# Motor_Driver_HIP4082_Board_V1_3.net
KiCad netlist of a schematic drawn in Altium Designer
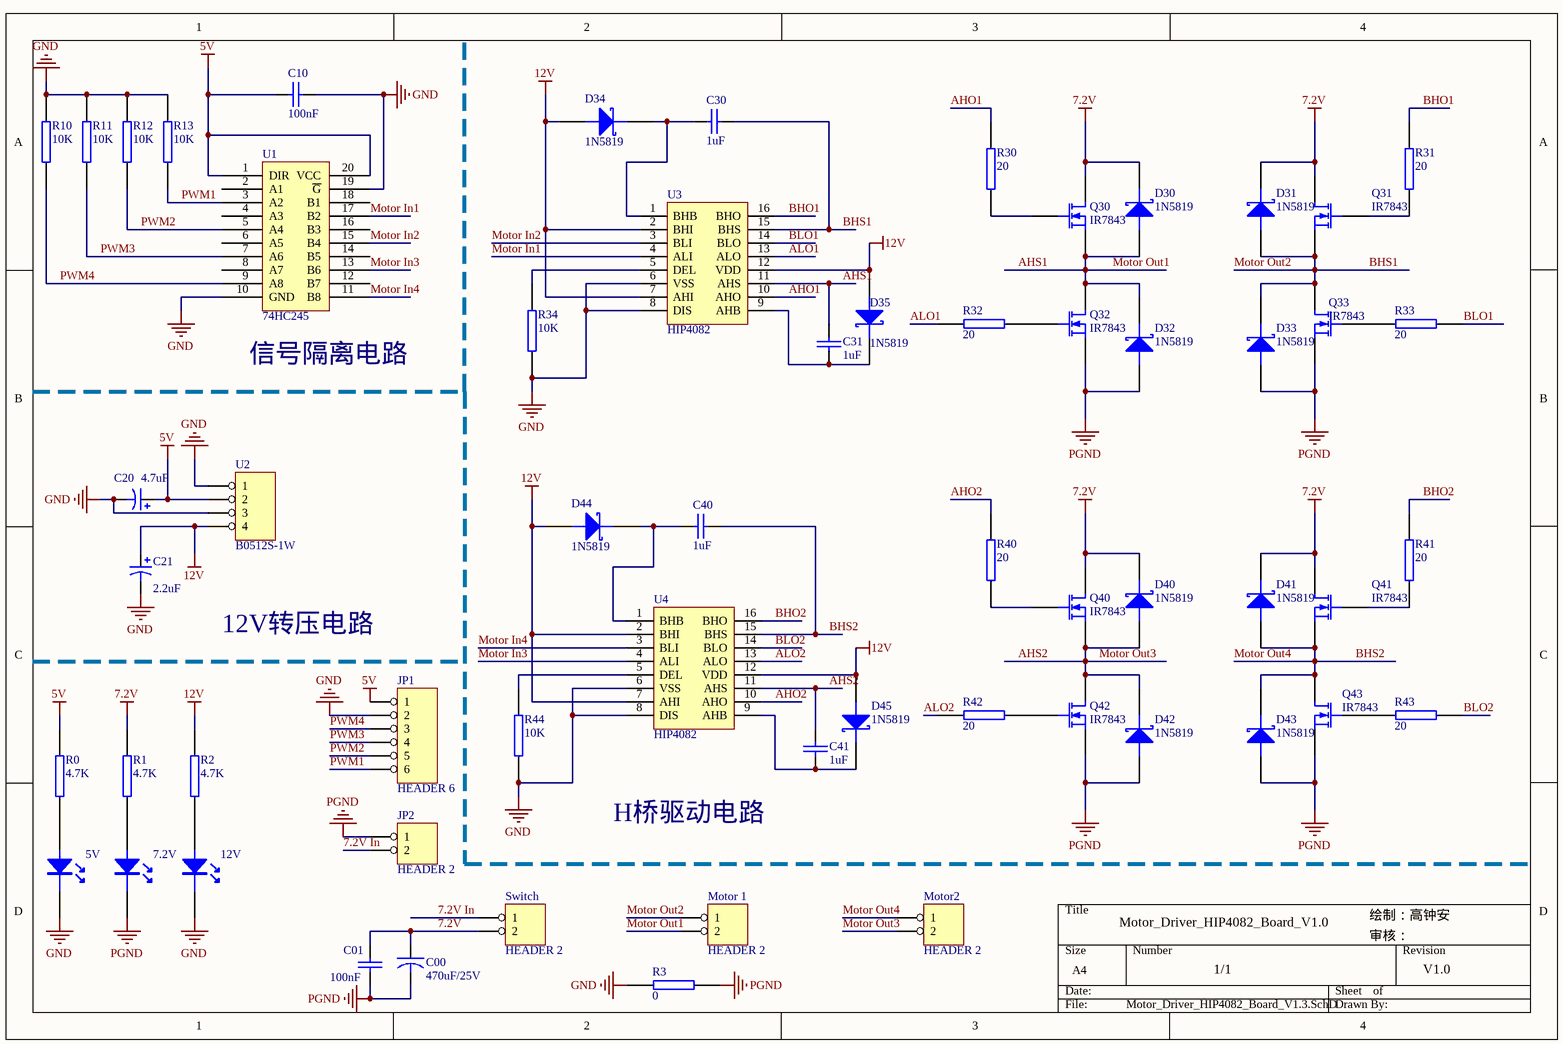
[diagram p0: Motor_Driver_HIP4082_Board_V1.3.SchDoc]

(export (version "E")
  (design (tool "Eeschema 10.0.6"))
  (components
    (comp (ref "5V") (value "~") (footprint "0805_LED_S1") (libsource (lib "Protel99Lib_SCH") (part "LED")))
    (comp (ref "7.2V") (value "~") (footprint "0805_LED_S1") (libsource (lib "Protel99Lib_SCH") (part "LED")))
    (comp (ref "12V") (value "~") (footprint "0805_LED_S1") (libsource (lib "Protel99Lib_SCH") (part "LED")))
    (comp (ref "C00")
      (value "470uF/25V")
      (footprint "RB.2/.4")
      (description "Capacitor")
      (libsource (lib "Protel99Lib_SCH") (part "CAPACITOR"))
    )
    (comp (ref "C01")
      (value "100nF")
      (footprint "0805C")
      (description "Capacitor")
      (libsource (lib "Protel99Lib_SCH") (part "CAP"))
    )
    (comp (ref "C10")
      (value "100nF")
      (footprint "0603_C")
      (description "Capacitor")
      (libsource (lib "Protel99Lib_SCH") (part "CAP"))
    )
    (comp (ref "C20")
      (value "4.7uF")
      (footprint "3528")
      (description "Polarized Capacitor (Surface Mount)")
      (fields (field (name "PUBLISHER") "Altium Limited"))
      (libsource (lib "Miscellaneous Devices") (part "Cap Pol3"))
    )
    (comp (ref "C21")
      (value "2.2uF")
      (footprint "3528")
      (description "Polarized Capacitor (Surface Mount)")
      (fields (field (name "PUBLISHER") "Altium Limited"))
      (libsource (lib "Miscellaneous Devices") (part "Cap Pol3"))
    )
    (comp (ref "C30")
      (value "1uF")
      (footprint "0603C")
      (description "Capacitor")
      (libsource (lib "Protel99Lib_SCH") (part "CAP"))
    )
    (comp (ref "C31")
      (value "1uF")
      (footprint "0603C")
      (description "Capacitor")
      (libsource (lib "Protel99Lib_SCH") (part "CAP"))
    )
    (comp (ref "C40")
      (value "1uF")
      (footprint "0603_C")
      (description "Capacitor")
      (libsource (lib "Protel99Lib_SCH") (part "CAP"))
    )
    (comp (ref "C41")
      (value "1uF")
      (footprint "0603_C")
      (description "Capacitor")
      (libsource (lib "Protel99Lib_SCH") (part "CAP"))
    )
    (comp (ref "D30")
      (value "1N5819")
      (footprint "SOD-323")
      (description "Schottky Diode")
      (libsource (lib "Protel99Lib_SCH") (part "DIODE SCHOTTKY"))
    )
    (comp (ref "D31")
      (value "1N5819")
      (footprint "SOD-323")
      (description "Schottky Diode")
      (libsource (lib "Protel99Lib_SCH") (part "DIODE SCHOTTKY"))
    )
    (comp (ref "D32")
      (value "1N5819")
      (footprint "SOD-323")
      (description "Schottky Diode")
      (libsource (lib "Protel99Lib_SCH") (part "DIODE SCHOTTKY"))
    )
    (comp (ref "D33")
      (value "1N5819")
      (footprint "SOD-323")
      (description "Schottky Diode")
      (libsource (lib "Protel99Lib_SCH") (part "DIODE SCHOTTKY"))
    )
    (comp (ref "D34")
      (value "1N5819")
      (footprint "SOD-323")
      (description "Schottky Diode")
      (libsource (lib "Protel99Lib_SCH") (part "DIODE SCHOTTKY"))
    )
    (comp (ref "D35")
      (value "1N5819")
      (footprint "SOD-323")
      (description "Schottky Diode")
      (libsource (lib "Protel99Lib_SCH") (part "DIODE SCHOTTKY"))
    )
    (comp (ref "D40")
      (value "1N5819")
      (footprint "SOD-323")
      (description "Schottky Diode")
      (libsource (lib "Protel99Lib_SCH") (part "DIODE SCHOTTKY"))
    )
    (comp (ref "D41")
      (value "1N5819")
      (footprint "SOD-323")
      (description "Schottky Diode")
      (libsource (lib "Protel99Lib_SCH") (part "DIODE SCHOTTKY"))
    )
    (comp (ref "D42")
      (value "1N5819")
      (footprint "SOD-323")
      (description "Schottky Diode")
      (libsource (lib "Protel99Lib_SCH") (part "DIODE SCHOTTKY"))
    )
    (comp (ref "D43")
      (value "1N5819")
      (footprint "SOD-323")
      (description "Schottky Diode")
      (libsource (lib "Protel99Lib_SCH") (part "DIODE SCHOTTKY"))
    )
    (comp (ref "D44")
      (value "1N5819")
      (footprint "SOD-323")
      (description "Schottky Diode")
      (libsource (lib "Protel99Lib_SCH") (part "DIODE SCHOTTKY"))
    )
    (comp (ref "D45")
      (value "1N5819")
      (footprint "SOD-323")
      (description "Schottky Diode")
      (libsource (lib "Protel99Lib_SCH") (part "DIODE SCHOTTKY"))
    )
    (comp (ref "JP1")
      (value "HEADER 6")
      (footprint "SIP6N")
      (libsource (lib "Protel99Lib_SCH") (part "HEADER 6"))
    )
    (comp (ref "JP2")
      (value "HEADER 2")
      (footprint "KF301-2P")
      (libsource (lib "Protel99Lib_SCH") (part "HEADER 2"))
    )
    (comp (ref "Motor 1")
      (value "HEADER 2")
      (footprint "KF301-2P")
      (libsource (lib "Protel99Lib_SCH") (part "HEADER 2"))
    )
    (comp (ref "Motor2")
      (value "HEADER 2")
      (footprint "KF301-2P")
      (libsource (lib "Protel99Lib_SCH") (part "HEADER 2"))
    )
    (comp (ref "Q30")
      (value "IR7843")
      (footprint "LR7843")
      (description "N-Channel MOSFET")
      (fields (field (name "PUBLISHER") "Altium Limited"))
      (libsource (lib "Miscellaneous Devices") (part "MOSFET-N"))
    )
    (comp (ref "Q31")
      (value "IR7843")
      (footprint "LR7843")
      (description "N-Channel MOSFET")
      (fields (field (name "PUBLISHER") "Altium Limited"))
      (libsource (lib "Miscellaneous Devices") (part "MOSFET-N"))
    )
    (comp (ref "Q32")
      (value "IR7843")
      (footprint "LR7843")
      (description "N-Channel MOSFET")
      (fields (field (name "PUBLISHER") "Altium Limited"))
      (libsource (lib "Miscellaneous Devices") (part "MOSFET-N"))
    )
    (comp (ref "Q33")
      (value "IR7843")
      (footprint "LR7843")
      (description "N-Channel MOSFET")
      (fields (field (name "PUBLISHER") "Altium Limited"))
      (libsource (lib "Miscellaneous Devices") (part "MOSFET-N"))
    )
    (comp (ref "Q40")
      (value "IR7843")
      (footprint "LR7843")
      (description "N-Channel MOSFET")
      (fields (field (name "PUBLISHER") "Altium Limited"))
      (libsource (lib "Miscellaneous Devices") (part "MOSFET-N"))
    )
    (comp (ref "Q41")
      (value "IR7843")
      (footprint "LR7843")
      (description "N-Channel MOSFET")
      (fields (field (name "PUBLISHER") "Altium Limited"))
      (libsource (lib "Miscellaneous Devices") (part "MOSFET-N"))
    )
    (comp (ref "Q42")
      (value "IR7843")
      (footprint "LR7843")
      (description "N-Channel MOSFET")
      (fields (field (name "PUBLISHER") "Altium Limited"))
      (libsource (lib "Miscellaneous Devices") (part "MOSFET-N"))
    )
    (comp (ref "Q43")
      (value "IR7843")
      (footprint "LR7843")
      (description "N-Channel MOSFET")
      (fields (field (name "PUBLISHER") "Altium Limited"))
      (libsource (lib "Miscellaneous Devices") (part "MOSFET-N"))
    )
    (comp (ref "R0") (value "4.7K") (footprint "0603_R") (libsource (lib "") (part "RES2_1")))
    (comp (ref "R1") (value "4.7K") (footprint "0603_R") (libsource (lib "") (part "RES2_1")))
    (comp (ref "R2") (value "4.7K") (footprint "0603_R") (libsource (lib "") (part "RES2_1")))
    (comp (ref "R3") (value "0") (footprint "0805") (libsource (lib "") (part "RES2_1")))
    (comp (ref "R10") (value "10K") (footprint "0603_R") (libsource (lib "Protel99Lib_SCH") (part "RES2")))
    (comp (ref "R11") (value "10K") (footprint "0603_R") (libsource (lib "Protel99Lib_SCH") (part "RES2")))
    (comp (ref "R12") (value "10K") (footprint "0603_R") (libsource (lib "Protel99Lib_SCH") (part "RES2")))
    (comp (ref "R13") (value "10K") (footprint "0603_R") (libsource (lib "Protel99Lib_SCH") (part "RES2")))
    (comp (ref "R30") (value "20") (footprint "0805") (libsource (lib "") (part "RES2_1")))
    (comp (ref "R31") (value "20") (footprint "0805") (libsource (lib "") (part "RES2_1")))
    (comp (ref "R32") (value "20") (footprint "0805") (libsource (lib "") (part "RES2_1")))
    (comp (ref "R33") (value "20") (footprint "0805") (libsource (lib "") (part "RES2_1")))
    (comp (ref "R34") (value "10K") (footprint "0603_R") (libsource (lib "") (part "RES2_1")))
    (comp (ref "R40") (value "20") (footprint "0805") (libsource (lib "") (part "RES2_1")))
    (comp (ref "R41") (value "20") (footprint "0805") (libsource (lib "") (part "RES2_1")))
    (comp (ref "R42") (value "20") (footprint "0805") (libsource (lib "") (part "RES2_1")))
    (comp (ref "R43") (value "20") (footprint "0805") (libsource (lib "") (part "RES2_1")))
    (comp (ref "R44") (value "10K") (footprint "0603_R") (libsource (lib "") (part "RES2_1")))
    (comp (ref "Switch")
      (value "HEADER 2")
      (footprint "SWITCH-MINI")
      (libsource (lib "Protel99Lib_SCH") (part "HEADER 2"))
    )
    (comp (ref "U1") (value "74HC245") (footprint "SOP20") (libsource (lib "BaseLib_SCH") (part "74HC245")))
    (comp (ref "U2")
      (value "B0512S-1W")
      (footprint "SIP4_B_S-1W")
      (description "4 Pin Header")
      (libsource (lib "Protel99Lib_SCH") (part "4 HEADER"))
    )
    (comp (ref "U3")
      (value "HIP4082")
      (footprint "SOP-16_208mil")
      (libsource (lib "Motor_Driver_HIP4082_Board_V1.0") (part "HIP4082"))
    )
    (comp (ref "U4")
      (value "HIP4082")
      (footprint "SOP-16_208mil")
      (libsource (lib "Motor_Driver_HIP4082_Board_V1.0") (part "HIP4082"))
    )
  )
  (nets
    (net (code "1") (name "/7.2V In") (class "Default")
      (node (ref "JP2") (pin "2") (pinfunction "2_2") (pintype "passive"))
      (node (ref "Switch") (pin "1") (pinfunction "1_1") (pintype "passive"))
    )
    (net (code "2") (name "/AHO1") (class "Default")
      (node (ref "R30") (pin "2") (pinfunction "2_2") (pintype "passive"))
      (node (ref "U3") (pin "10") (pinfunction "AHO_10") (pintype "passive"))
    )
    (net (code "3") (name "/AHO2") (class "Default")
      (node (ref "R40") (pin "2") (pinfunction "2_2") (pintype "passive"))
      (node (ref "U4") (pin "10") (pinfunction "AHO_10") (pintype "passive"))
    )
    (net (code "4") (name "/AHS1") (class "Default")
      (node (ref "C31") (pin "2") (pinfunction "2_2") (pintype "passive"))
      (node (ref "D30") (pin "1") (pinfunction "A_1") (pintype "passive"))
      (node (ref "D32") (pin "2") (pinfunction "K_2") (pintype "passive"))
      (node (ref "Motor 1") (pin "2") (pinfunction "2_2") (pintype "passive"))
      (node (ref "Q30") (pin "3") (pinfunction "S_3") (pintype "passive"))
      (node (ref "Q32") (pin "1") (pinfunction "D_1") (pintype "passive"))
      (node (ref "U3") (pin "11") (pinfunction "AHS_11") (pintype "passive"))
    )
    (net (code "5") (name "/AHS2") (class "Default")
      (node (ref "C41") (pin "2") (pinfunction "2_2") (pintype "passive"))
      (node (ref "D40") (pin "1") (pinfunction "A_1") (pintype "passive"))
      (node (ref "D42") (pin "2") (pinfunction "K_2") (pintype "passive"))
      (node (ref "Motor2") (pin "2") (pinfunction "2_2") (pintype "passive"))
      (node (ref "Q40") (pin "3") (pinfunction "S_3") (pintype "passive"))
      (node (ref "Q42") (pin "1") (pinfunction "D_1") (pintype "passive"))
      (node (ref "U4") (pin "11") (pinfunction "AHS_11") (pintype "passive"))
    )
    (net (code "6") (name "/ALO1") (class "Default")
      (node (ref "R32") (pin "2") (pinfunction "2_2") (pintype "passive"))
      (node (ref "U3") (pin "13") (pinfunction "ALO_13") (pintype "passive"))
    )
    (net (code "7") (name "/ALO2") (class "Default")
      (node (ref "R42") (pin "2") (pinfunction "2_2") (pintype "passive"))
      (node (ref "U4") (pin "13") (pinfunction "ALO_13") (pintype "passive"))
    )
    (net (code "8") (name "/BHO1") (class "Default")
      (node (ref "R31") (pin "2") (pinfunction "2_2") (pintype "passive"))
      (node (ref "U3") (pin "16") (pinfunction "BHO_16") (pintype "passive"))
    )
    (net (code "9") (name "/BHO2") (class "Default")
      (node (ref "R41") (pin "2") (pinfunction "2_2") (pintype "passive"))
      (node (ref "U4") (pin "16") (pinfunction "BHO_16") (pintype "passive"))
    )
    (net (code "10") (name "/BHS1") (class "Default")
      (node (ref "C30") (pin "2") (pinfunction "2_2") (pintype "passive"))
      (node (ref "D31") (pin "1") (pinfunction "A_1") (pintype "passive"))
      (node (ref "D33") (pin "2") (pinfunction "K_2") (pintype "passive"))
      (node (ref "Motor 1") (pin "1") (pinfunction "1_1") (pintype "passive"))
      (node (ref "Q31") (pin "3") (pinfunction "S_3") (pintype "passive"))
      (node (ref "Q33") (pin "1") (pinfunction "D_1") (pintype "passive"))
      (node (ref "U3") (pin "15") (pinfunction "BHS_15") (pintype "passive"))
    )
    (net (code "11") (name "/BHS2") (class "Default")
      (node (ref "C40") (pin "2") (pinfunction "2_2") (pintype "passive"))
      (node (ref "D41") (pin "1") (pinfunction "A_1") (pintype "passive"))
      (node (ref "D43") (pin "2") (pinfunction "K_2") (pintype "passive"))
      (node (ref "Motor2") (pin "1") (pinfunction "1_1") (pintype "passive"))
      (node (ref "Q41") (pin "3") (pinfunction "S_3") (pintype "passive"))
      (node (ref "Q43") (pin "1") (pinfunction "D_1") (pintype "passive"))
      (node (ref "U4") (pin "15") (pinfunction "BHS_15") (pintype "passive"))
    )
    (net (code "12") (name "/BLO1") (class "Default")
      (node (ref "R33") (pin "1") (pinfunction "1_1") (pintype "passive"))
      (node (ref "U3") (pin "14") (pinfunction "BLO_14") (pintype "passive"))
    )
    (net (code "13") (name "/BLO2") (class "Default")
      (node (ref "R43") (pin "1") (pinfunction "1_1") (pintype "passive"))
      (node (ref "U4") (pin "14") (pinfunction "BLO_14") (pintype "passive"))
    )
    (net (code "14") (name "/Motor In1") (class "Default")
      (node (ref "U1") (pin "17") (pinfunction "B2_17") (pintype "passive"))
      (node (ref "U3") (pin "4") (pinfunction "ALI_4") (pintype "passive"))
    )
    (net (code "15") (name "/Motor In2") (class "Default")
      (node (ref "U1") (pin "15") (pinfunction "B4_15") (pintype "passive"))
      (node (ref "U3") (pin "3") (pinfunction "BLI_3") (pintype "passive"))
    )
    (net (code "16") (name "/Motor In3") (class "Default")
      (node (ref "U1") (pin "13") (pinfunction "B6_13") (pintype "passive"))
      (node (ref "U4") (pin "4") (pinfunction "ALI_4") (pintype "passive"))
    )
    (net (code "17") (name "/Motor In4") (class "Default")
      (node (ref "U1") (pin "11") (pinfunction "B8_11") (pintype "passive"))
      (node (ref "U4") (pin "3") (pinfunction "BLI_3") (pintype "passive"))
    )
    (net (code "18") (name "/PWM1") (class "Default")
      (node (ref "JP1") (pin "6") (pinfunction "6_6") (pintype "passive"))
      (node (ref "R13") (pin "1") (pinfunction "1_1") (pintype "passive"))
      (node (ref "U1") (pin "3") (pinfunction "A2_3") (pintype "passive"))
    )
    (net (code "19") (name "/PWM2") (class "Default")
      (node (ref "JP1") (pin "5") (pinfunction "5_5") (pintype "passive"))
      (node (ref "R12") (pin "1") (pinfunction "1_1") (pintype "passive"))
      (node (ref "U1") (pin "5") (pinfunction "A4_5") (pintype "passive"))
    )
    (net (code "20") (name "/PWM3") (class "Default")
      (node (ref "JP1") (pin "4") (pinfunction "4_4") (pintype "passive"))
      (node (ref "R11") (pin "2") (pinfunction "2_2") (pintype "passive"))
      (node (ref "U1") (pin "7") (pinfunction "A6_7") (pintype "passive"))
    )
    (net (code "21") (name "/PWM4") (class "Default")
      (node (ref "JP1") (pin "3") (pinfunction "3_3") (pintype "passive"))
      (node (ref "R10") (pin "1") (pinfunction "1_1") (pintype "passive"))
      (node (ref "U1") (pin "9") (pinfunction "A8_9") (pintype "passive"))
    )
    (net (code "22") (name "5V") (class "Default")
      (node (ref "C10") (pin "1") (pinfunction "1_1") (pintype "passive"))
      (node (ref "C20") (pin "1") (pinfunction "1_1") (pintype "passive"))
      (node (ref "JP1") (pin "1") (pinfunction "1_1") (pintype "passive"))
      (node (ref "R0") (pin "2") (pinfunction "2_2") (pintype "passive"))
      (node (ref "U1") (pin "1") (pinfunction "DIR_1") (pintype "passive"))
      (node (ref "U1") (pin "20") (pinfunction "VCC_20") (pintype "passive"))
      (node (ref "U2") (pin "2") (pinfunction "2_2") (pintype "passive"))
    )
    (net (code "23") (name "7.2V") (class "Default")
      (node (ref "C00") (pin "1") (pinfunction "1_1") (pintype "passive"))
      (node (ref "C01") (pin "2") (pinfunction "2_2") (pintype "passive"))
      (node (ref "D30") (pin "2") (pinfunction "K_2") (pintype "passive"))
      (node (ref "D31") (pin "2") (pinfunction "K_2") (pintype "passive"))
      (node (ref "D40") (pin "2") (pinfunction "K_2") (pintype "passive"))
      (node (ref "D41") (pin "2") (pinfunction "K_2") (pintype "passive"))
      (node (ref "Q30") (pin "1") (pinfunction "D_1") (pintype "passive"))
      (node (ref "Q31") (pin "1") (pinfunction "D_1") (pintype "passive"))
      (node (ref "Q40") (pin "1") (pinfunction "D_1") (pintype "passive"))
      (node (ref "Q41") (pin "1") (pinfunction "D_1") (pintype "passive"))
      (node (ref "R1") (pin "2") (pinfunction "2_2") (pintype "passive"))
      (node (ref "Switch") (pin "2") (pinfunction "2_2") (pintype "passive"))
    )
    (net (code "24") (name "12V") (class "Default")
      (node (ref "C21") (pin "1") (pinfunction "1_1") (pintype "passive"))
      (node (ref "D34") (pin "1") (pinfunction "A_1") (pintype "passive"))
      (node (ref "D35") (pin "1") (pinfunction "A_1") (pintype "passive"))
      (node (ref "D44") (pin "1") (pinfunction "A_1") (pintype "passive"))
      (node (ref "D45") (pin "1") (pinfunction "A_1") (pintype "passive"))
      (node (ref "R2") (pin "2") (pinfunction "2_2") (pintype "passive"))
      (node (ref "U2") (pin "4") (pinfunction "4_4") (pintype "passive"))
      (node (ref "U3") (pin "12") (pinfunction "VDD_12") (pintype "passive"))
      (node (ref "U3") (pin "2") (pinfunction "BHI_2") (pintype "passive"))
      (node (ref "U3") (pin "7") (pinfunction "AHI_7") (pintype "passive"))
      (node (ref "U4") (pin "12") (pinfunction "VDD_12") (pintype "passive"))
      (node (ref "U4") (pin "2") (pinfunction "BHI_2") (pintype "passive"))
      (node (ref "U4") (pin "7") (pinfunction "AHI_7") (pintype "passive"))
    )
    (net (code "25") (name "GND") (class "Default")
      (node (ref "12V") (pin "K") (pinfunction "2_K") (pintype "passive"))
      (node (ref "5V") (pin "K") (pinfunction "2_K") (pintype "passive"))
      (node (ref "C10") (pin "2") (pinfunction "2_2") (pintype "passive"))
      (node (ref "C20") (pin "2") (pinfunction "2_2") (pintype "passive"))
      (node (ref "C21") (pin "2") (pinfunction "2_2") (pintype "passive"))
      (node (ref "JP1") (pin "2") (pinfunction "2_2") (pintype "passive"))
      (node (ref "R10") (pin "2") (pinfunction "2_2") (pintype "passive"))
      (node (ref "R11") (pin "1") (pinfunction "1_1") (pintype "passive"))
      (node (ref "R12") (pin "2") (pinfunction "2_2") (pintype "passive"))
      (node (ref "R13") (pin "2") (pinfunction "2_2") (pintype "passive"))
      (node (ref "R3") (pin "2") (pinfunction "2_2") (pintype "passive"))
      (node (ref "R34") (pin "1") (pinfunction "1_1") (pintype "passive"))
      (node (ref "R44") (pin "1") (pinfunction "1_1") (pintype "passive"))
      (node (ref "U1") (pin "10") (pinfunction "GND_10") (pintype "passive"))
      (node (ref "U1") (pin "19") (pinfunction "~{G}_19") (pintype "passive"))
      (node (ref "U2") (pin "1") (pinfunction "1_1") (pintype "passive"))
      (node (ref "U2") (pin "3") (pinfunction "3_3") (pintype "passive"))
      (node (ref "U3") (pin "6") (pinfunction "VSS_6") (pintype "passive"))
      (node (ref "U3") (pin "8") (pinfunction "DIS_8") (pintype "passive"))
      (node (ref "U4") (pin "6") (pinfunction "VSS_6") (pintype "passive"))
      (node (ref "U4") (pin "8") (pinfunction "DIS_8") (pintype "passive"))
    )
    (net (code "26") (name "Net-(5V-1)") (class "Default")
      (node (ref "5V") (pin "A") (pinfunction "1_A") (pintype "passive"))
      (node (ref "R0") (pin "1") (pinfunction "1_1") (pintype "passive"))
    )
    (net (code "27") (name "Net-(7.2V-1)") (class "Default")
      (node (ref "7.2V") (pin "A") (pinfunction "1_A") (pintype "passive"))
      (node (ref "R1") (pin "1") (pinfunction "1_1") (pintype "passive"))
    )
    (net (code "28") (name "Net-(12V-1)") (class "Default")
      (node (ref "12V") (pin "A") (pinfunction "1_A") (pintype "passive"))
      (node (ref "R2") (pin "1") (pinfunction "1_1") (pintype "passive"))
    )
    (net (code "29") (name "Net-(D34-K)") (class "Default")
      (node (ref "C30") (pin "1") (pinfunction "1_1") (pintype "passive"))
      (node (ref "D34") (pin "2") (pinfunction "K_2") (pintype "passive"))
      (node (ref "U3") (pin "1") (pinfunction "BHB_1") (pintype "passive"))
    )
    (net (code "30") (name "Net-(D35-K)") (class "Default")
      (node (ref "C31") (pin "1") (pinfunction "1_1") (pintype "passive"))
      (node (ref "D35") (pin "2") (pinfunction "K_2") (pintype "passive"))
      (node (ref "U3") (pin "9") (pinfunction "AHB_9") (pintype "passive"))
    )
    (net (code "31") (name "Net-(D44-K)") (class "Default")
      (node (ref "C40") (pin "1") (pinfunction "1_1") (pintype "passive"))
      (node (ref "D44") (pin "2") (pinfunction "K_2") (pintype "passive"))
      (node (ref "U4") (pin "1") (pinfunction "BHB_1") (pintype "passive"))
    )
    (net (code "32") (name "Net-(D45-K)") (class "Default")
      (node (ref "C41") (pin "1") (pinfunction "1_1") (pintype "passive"))
      (node (ref "D45") (pin "2") (pinfunction "K_2") (pintype "passive"))
      (node (ref "U4") (pin "9") (pinfunction "AHB_9") (pintype "passive"))
    )
    (net (code "33") (name "Net-(Q30-G)") (class "Default")
      (node (ref "Q30") (pin "2") (pinfunction "G_2") (pintype "passive"))
      (node (ref "R30") (pin "1") (pinfunction "1_1") (pintype "passive"))
    )
    (net (code "34") (name "Net-(Q31-G)") (class "Default")
      (node (ref "Q31") (pin "2") (pinfunction "G_2") (pintype "passive"))
      (node (ref "R31") (pin "1") (pinfunction "1_1") (pintype "passive"))
    )
    (net (code "35") (name "Net-(Q32-G)") (class "Default")
      (node (ref "Q32") (pin "2") (pinfunction "G_2") (pintype "passive"))
      (node (ref "R32") (pin "1") (pinfunction "1_1") (pintype "passive"))
    )
    (net (code "36") (name "Net-(Q33-G)") (class "Default")
      (node (ref "Q33") (pin "2") (pinfunction "G_2") (pintype "passive"))
      (node (ref "R33") (pin "2") (pinfunction "2_2") (pintype "passive"))
    )
    (net (code "37") (name "Net-(Q40-G)") (class "Default")
      (node (ref "Q40") (pin "2") (pinfunction "G_2") (pintype "passive"))
      (node (ref "R40") (pin "1") (pinfunction "1_1") (pintype "passive"))
    )
    (net (code "38") (name "Net-(Q41-G)") (class "Default")
      (node (ref "Q41") (pin "2") (pinfunction "G_2") (pintype "passive"))
      (node (ref "R41") (pin "1") (pinfunction "1_1") (pintype "passive"))
    )
    (net (code "39") (name "Net-(Q42-G)") (class "Default")
      (node (ref "Q42") (pin "2") (pinfunction "G_2") (pintype "passive"))
      (node (ref "R42") (pin "1") (pinfunction "1_1") (pintype "passive"))
    )
    (net (code "40") (name "Net-(Q43-G)") (class "Default")
      (node (ref "Q43") (pin "2") (pinfunction "G_2") (pintype "passive"))
      (node (ref "R43") (pin "2") (pinfunction "2_2") (pintype "passive"))
    )
    (net (code "41") (name "Net-(U3-DEL)") (class "Default")
      (node (ref "R34") (pin "2") (pinfunction "2_2") (pintype "passive"))
      (node (ref "U3") (pin "5") (pinfunction "DEL_5") (pintype "passive"))
    )
    (net (code "42") (name "Net-(U4-DEL)") (class "Default")
      (node (ref "R44") (pin "2") (pinfunction "2_2") (pintype "passive"))
      (node (ref "U4") (pin "5") (pinfunction "DEL_5") (pintype "passive"))
    )
    (net (code "43") (name "PGND") (class "Default")
      (node (ref "7.2V") (pin "K") (pinfunction "2_K") (pintype "passive"))
      (node (ref "C00") (pin "2") (pinfunction "2_2") (pintype "passive"))
      (node (ref "C01") (pin "1") (pinfunction "1_1") (pintype "passive"))
      (node (ref "D32") (pin "1") (pinfunction "A_1") (pintype "passive"))
      (node (ref "D33") (pin "1") (pinfunction "A_1") (pintype "passive"))
      (node (ref "D42") (pin "1") (pinfunction "A_1") (pintype "passive"))
      (node (ref "D43") (pin "1") (pinfunction "A_1") (pintype "passive"))
      (node (ref "JP2") (pin "1") (pinfunction "1_1") (pintype "passive"))
      (node (ref "Q32") (pin "3") (pinfunction "S_3") (pintype "passive"))
      (node (ref "Q33") (pin "3") (pinfunction "S_3") (pintype "passive"))
      (node (ref "Q42") (pin "3") (pinfunction "S_3") (pintype "passive"))
      (node (ref "Q43") (pin "3") (pinfunction "S_3") (pintype "passive"))
      (node (ref "R3") (pin "1") (pinfunction "1_1") (pintype "passive"))
    )
    (net (code "44") (name "unconnected-(U1-A1-Pad2)") (class "Default")
      (node (ref "U1") (pin "2") (pinfunction "A1_2") (pintype "passive"))
    )
    (net (code "45") (name "unconnected-(U1-A3-Pad4)") (class "Default")
      (node (ref "U1") (pin "4") (pinfunction "A3_4") (pintype "passive"))
    )
    (net (code "46") (name "unconnected-(U1-A5-Pad6)") (class "Default")
      (node (ref "U1") (pin "6") (pinfunction "A5_6") (pintype "passive"))
    )
    (net (code "47") (name "unconnected-(U1-A7-Pad8)") (class "Default")
      (node (ref "U1") (pin "8") (pinfunction "A7_8") (pintype "passive"))
    )
    (net (code "48") (name "unconnected-(U1-B1-Pad18)") (class "Default")
      (node (ref "U1") (pin "18") (pinfunction "B1_18") (pintype "passive"))
    )
    (net (code "49") (name "unconnected-(U1-B3-Pad16)") (class "Default")
      (node (ref "U1") (pin "16") (pinfunction "B3_16") (pintype "passive"))
    )
    (net (code "50") (name "unconnected-(U1-B5-Pad14)") (class "Default")
      (node (ref "U1") (pin "14") (pinfunction "B5_14") (pintype "passive"))
    )
    (net (code "51") (name "unconnected-(U1-B7-Pad12)") (class "Default")
      (node (ref "U1") (pin "12") (pinfunction "B7_12") (pintype "passive"))
    )
  )
)
